# 15_-MAIN_CONNECTORS.net
KiCad netlist of a schematic drawn in Altium Designer
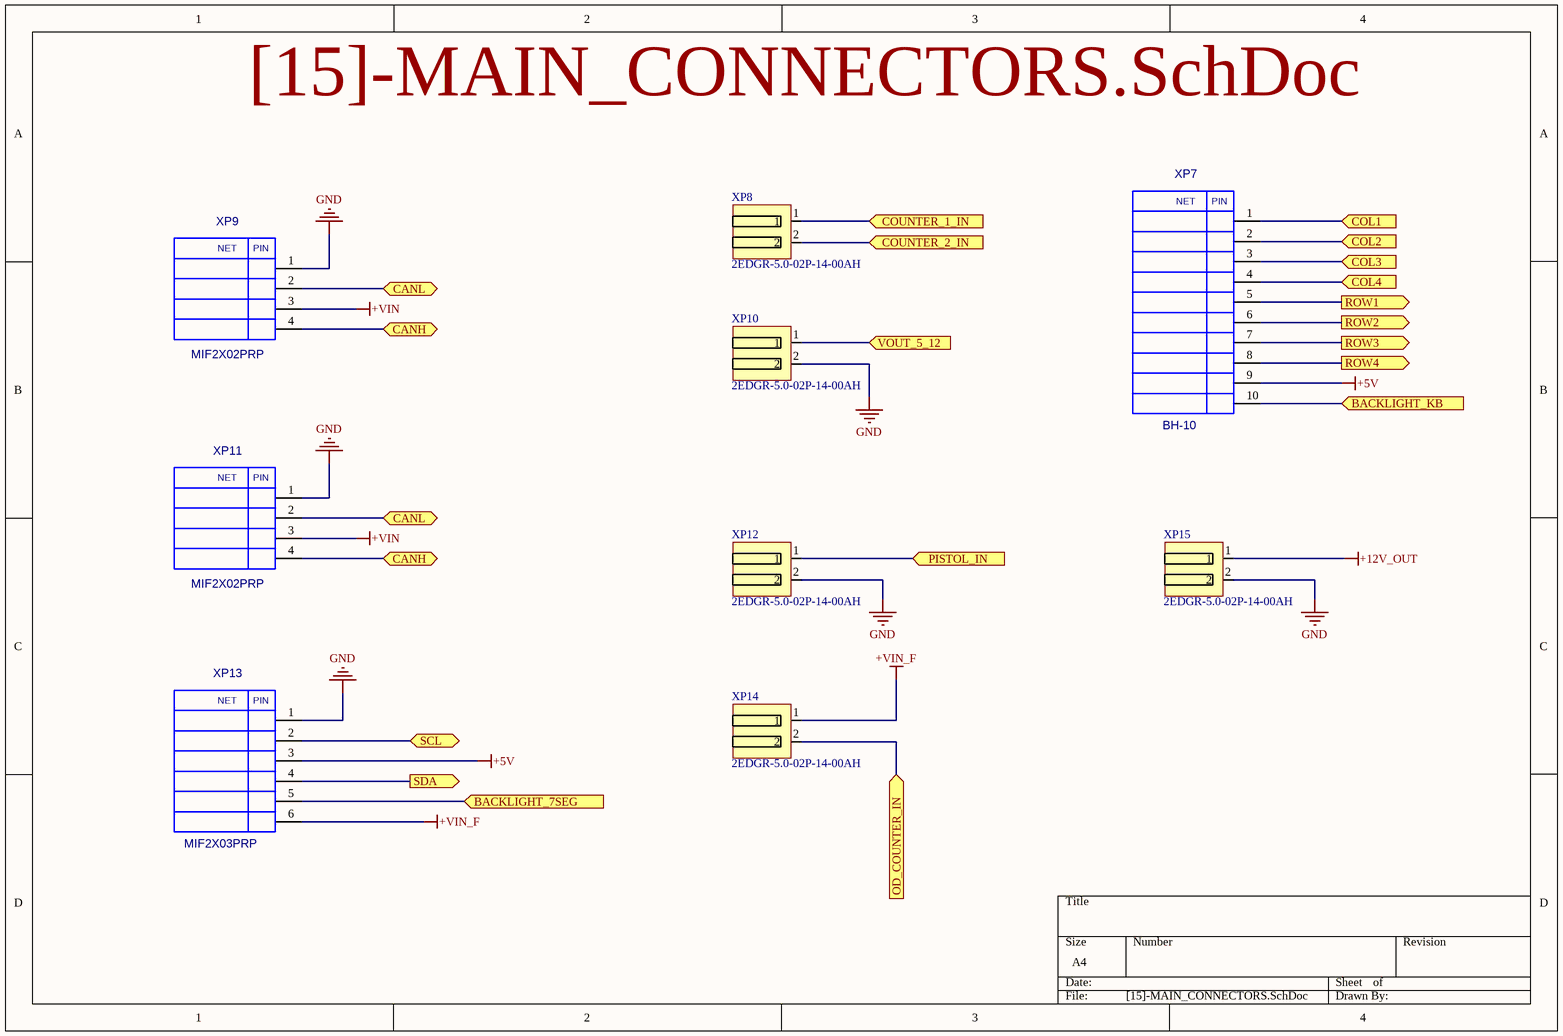
[diagram p0: [15]-MAIN_CONNECTORS.SchDoc]

(export (version "E")
  (design (tool "Eeschema 10.0.6"))
  (components
    (comp (ref "XP7") (value "BH-10") (footprint "BH-10") (libsource (lib "fizik_lib") (part "BH-10")))
    (comp (ref "XP8")
      (value "2EDGR-5.0-02P-14-00AH")
      (footprint "2EDGR-5.0")
      (libsource (lib "fizik_lib") (part "2EDGR-5.0-02P-14-00AH"))
    )
    (comp (ref "XP9")
      (value "MIF2X02PRP")
      (footprint "MIF2X02PRP")
      (libsource (lib "fizik_lib") (part "MIF2X02PRP"))
    )
    (comp (ref "XP10")
      (value "2EDGR-5.0-02P-14-00AH")
      (footprint "2EDGR-5.0")
      (libsource (lib "fizik_lib") (part "2EDGR-5.0-02P-14-00AH"))
    )
    (comp (ref "XP11")
      (value "MIF2X02PRP")
      (footprint "MIF2X02PRP")
      (libsource (lib "fizik_lib") (part "MIF2X02PRP"))
    )
    (comp (ref "XP12")
      (value "2EDGR-5.0-02P-14-00AH")
      (footprint "2EDGR-5.0")
      (libsource (lib "fizik_lib") (part "2EDGR-5.0-02P-14-00AH"))
    )
    (comp (ref "XP13")
      (value "MIF2X03PRP")
      (footprint "MIF2X03PRP")
      (libsource (lib "fizik_lib") (part "MIF2X03PRP"))
    )
    (comp (ref "XP14")
      (value "2EDGR-5.0-02P-14-00AH")
      (footprint "2EDGR-5.0")
      (libsource (lib "fizik_lib") (part "2EDGR-5.0-02P-14-00AH"))
    )
    (comp (ref "XP15")
      (value "2EDGR-5.0-02P-14-00AH")
      (footprint "2EDGR-5.0")
      (libsource (lib "fizik_lib") (part "2EDGR-5.0-02P-14-00AH"))
    )
  )
  (nets
    (net (code "1") (name "+5V") (class "Default")
      (node (ref "XP13") (pin "3") (pinfunction "3_3") (pintype "passive"))
      (node (ref "XP7") (pin "9") (pinfunction "9_9") (pintype "passive"))
    )
    (net (code "2") (name "+12V_OUT") (class "Default")
      (node (ref "XP15") (pin "1") (pinfunction "1_1") (pintype "passive"))
    )
    (net (code "3") (name "+VIN") (class "Default")
      (node (ref "XP11") (pin "3") (pinfunction "3_3") (pintype "passive"))
      (node (ref "XP9") (pin "3") (pinfunction "3_3") (pintype "passive"))
    )
    (net (code "4") (name "+VIN_F") (class "Default")
      (node (ref "XP13") (pin "6") (pinfunction "6_6") (pintype "passive"))
      (node (ref "XP14") (pin "1") (pinfunction "1_1") (pintype "passive"))
    )
    (net (code "5") (name "/BACKLIGHT_7SEG") (class "Default")
      (node (ref "XP13") (pin "5") (pinfunction "5_5") (pintype "passive"))
    )
    (net (code "6") (name "/BACKLIGHT_KB") (class "Default")
      (node (ref "XP7") (pin "10") (pinfunction "10_10") (pintype "passive"))
    )
    (net (code "7") (name "/CANH") (class "Default")
      (node (ref "XP11") (pin "4") (pinfunction "4_4") (pintype "passive"))
      (node (ref "XP9") (pin "4") (pinfunction "4_4") (pintype "passive"))
    )
    (net (code "8") (name "/CANL") (class "Default")
      (node (ref "XP11") (pin "2") (pinfunction "2_2") (pintype "passive"))
      (node (ref "XP9") (pin "2") (pinfunction "2_2") (pintype "passive"))
    )
    (net (code "9") (name "/COL1") (class "Default")
      (node (ref "XP7") (pin "1") (pinfunction "1_1") (pintype "passive"))
    )
    (net (code "10") (name "/COL2") (class "Default")
      (node (ref "XP7") (pin "2") (pinfunction "2_2") (pintype "passive"))
    )
    (net (code "11") (name "/COL3") (class "Default")
      (node (ref "XP7") (pin "3") (pinfunction "3_3") (pintype "passive"))
    )
    (net (code "12") (name "/COL4") (class "Default")
      (node (ref "XP7") (pin "4") (pinfunction "4_4") (pintype "passive"))
    )
    (net (code "13") (name "/COUNTER_1_IN") (class "Default")
      (node (ref "XP8") (pin "1") (pinfunction "1_1") (pintype "passive"))
    )
    (net (code "14") (name "/COUNTER_2_IN") (class "Default")
      (node (ref "XP8") (pin "2") (pinfunction "2_2") (pintype "passive"))
    )
    (net (code "15") (name "/OD_COUNTER_IN") (class "Default")
      (node (ref "XP14") (pin "2") (pinfunction "2_2") (pintype "passive"))
    )
    (net (code "16") (name "/PISTOL_IN") (class "Default")
      (node (ref "XP12") (pin "1") (pinfunction "1_1") (pintype "passive"))
    )
    (net (code "17") (name "/ROW1") (class "Default")
      (node (ref "XP7") (pin "5") (pinfunction "5_5") (pintype "passive"))
    )
    (net (code "18") (name "/ROW2") (class "Default")
      (node (ref "XP7") (pin "6") (pinfunction "6_6") (pintype "passive"))
    )
    (net (code "19") (name "/ROW3") (class "Default")
      (node (ref "XP7") (pin "7") (pinfunction "7_7") (pintype "passive"))
    )
    (net (code "20") (name "/ROW4") (class "Default")
      (node (ref "XP7") (pin "8") (pinfunction "8_8") (pintype "passive"))
    )
    (net (code "21") (name "/SCL") (class "Default")
      (node (ref "XP13") (pin "2") (pinfunction "2_2") (pintype "passive"))
    )
    (net (code "22") (name "/SDA") (class "Default")
      (node (ref "XP13") (pin "4") (pinfunction "4_4") (pintype "passive"))
    )
    (net (code "23") (name "/VOUT_5_12") (class "Default")
      (node (ref "XP10") (pin "1") (pinfunction "1_1") (pintype "passive"))
    )
    (net (code "24") (name "GND") (class "Default")
      (node (ref "XP10") (pin "2") (pinfunction "2_2") (pintype "passive"))
      (node (ref "XP11") (pin "1") (pinfunction "1_1") (pintype "passive"))
      (node (ref "XP12") (pin "2") (pinfunction "2_2") (pintype "passive"))
      (node (ref "XP13") (pin "1") (pinfunction "1_1") (pintype "passive"))
      (node (ref "XP15") (pin "2") (pinfunction "2_2") (pintype "passive"))
      (node (ref "XP9") (pin "1") (pinfunction "1_1") (pintype "passive"))
    )
  )
)
